# digipots.net
KiCad netlist of a schematic drawn in EAGLE
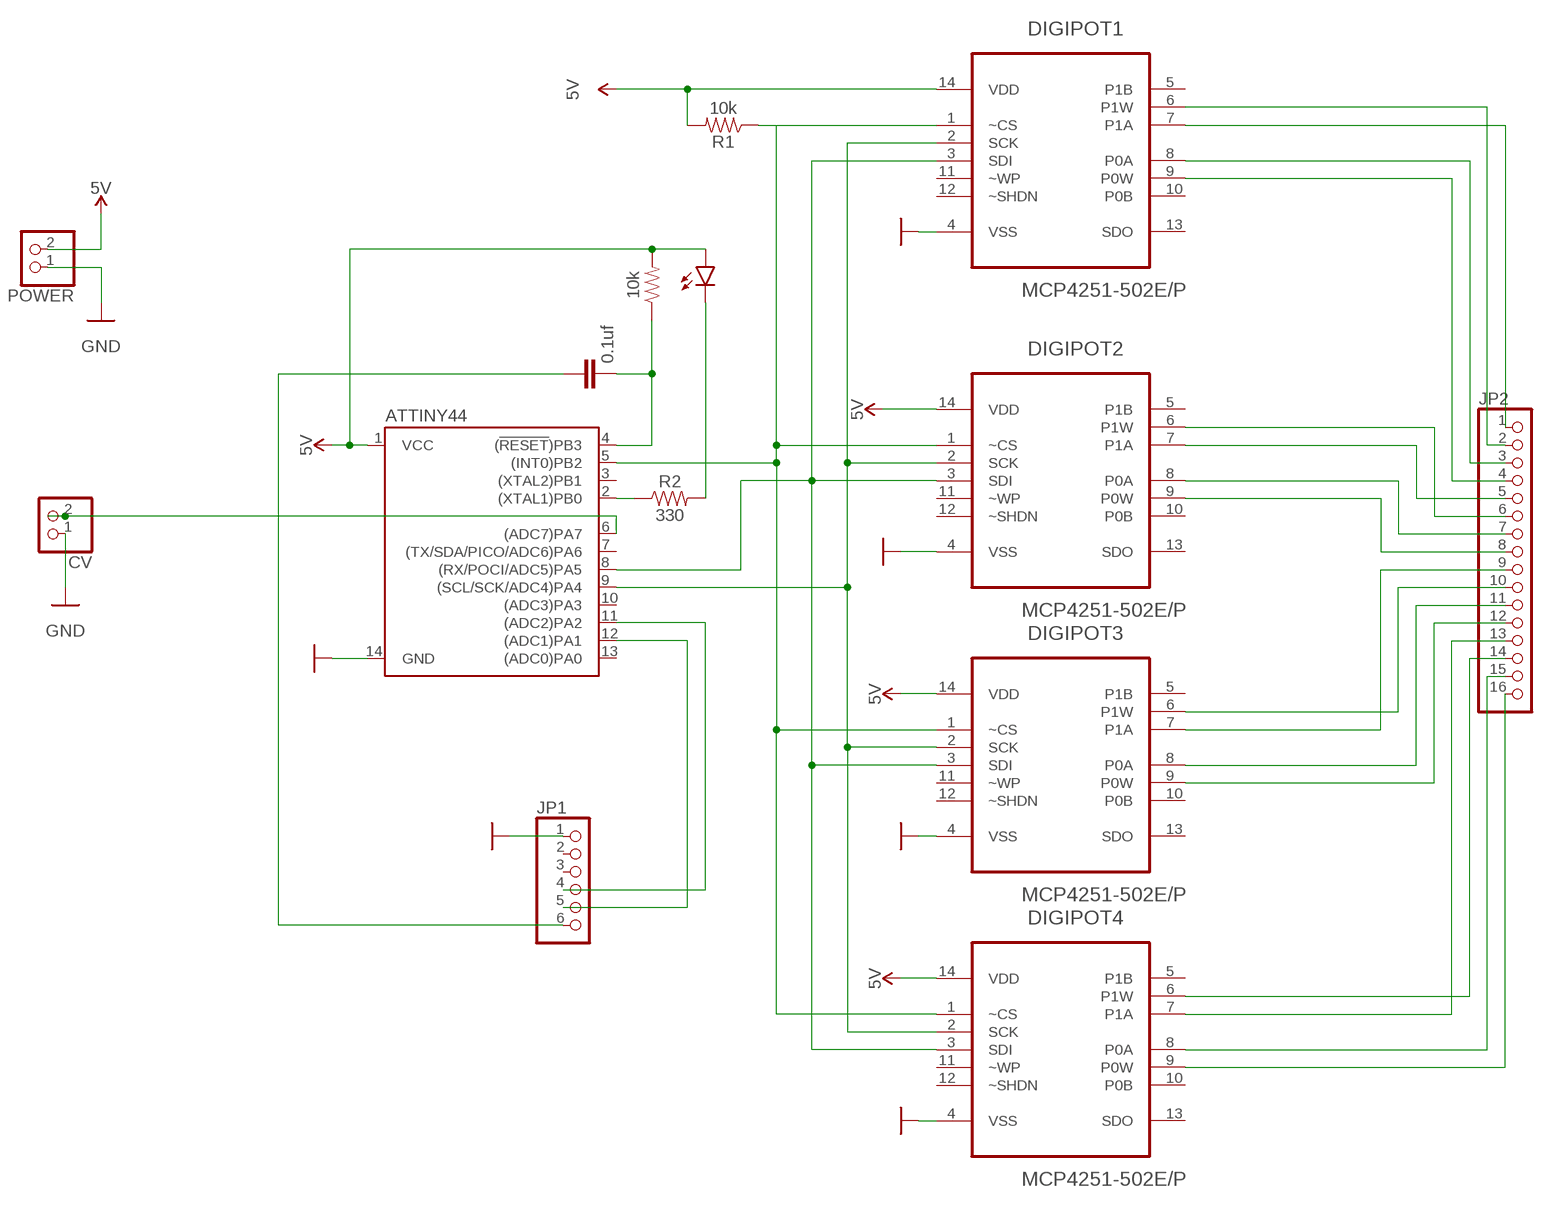
[diagram p0: schematic, sheet 1]

(export (version "E")
  (design (tool "Eeschema 10.0.6"))
  (components
    (comp (ref "ATTINY44")
      (value "ATTINY84ATTINY84-20PU")
      (footprint "eagle-import:DIP14")
      (libsource (lib "eagle-import") (part "ATTINY84ATTINY84-20PU"))
    )
    (comp (ref "C2")
      (value "0.1uf")
      (footprint "eagle-import:C025-024X044")
      (libsource (lib "eagle-import") (part "C-EU025-024X044"))
    )
    (comp (ref "CV")
      (value "PINHD-1X2")
      (footprint "eagle-import:1X02")
      (libsource (lib "eagle-import") (part "PINHD-1X2"))
    )
    (comp (ref "D1")
      (value "LED-5MM-KIT-NO-SILK")
      (footprint "eagle-import:LED_5MM-KIT-NO-SILK")
      (libsource (lib "eagle-import") (part "LED-5MM-KIT-NO-SILK"))
    )
    (comp (ref "DIGIPOT1")
      (value "MCP4251-502E/P")
      (footprint "eagle-import:DIP254P762X533-14")
      (fields (field (name "MF") "Microchip"))
      (libsource (lib "eagle-import") (part "MCP4251-502E/P"))
    )
    (comp (ref "DIGIPOT2")
      (value "MCP4251-502E/P")
      (footprint "eagle-import:DIP254P762X533-14")
      (fields (field (name "MF") "Microchip"))
      (libsource (lib "eagle-import") (part "MCP4251-502E/P"))
    )
    (comp (ref "DIGIPOT3")
      (value "MCP4251-502E/P")
      (footprint "eagle-import:DIP254P762X533-14")
      (fields (field (name "MF") "Microchip"))
      (libsource (lib "eagle-import") (part "MCP4251-502E/P"))
    )
    (comp (ref "DIGIPOT4")
      (value "MCP4251-502E/P")
      (footprint "eagle-import:DIP254P762X533-14")
      (fields (field (name "MF") "Microchip"))
      (libsource (lib "eagle-import") (part "MCP4251-502E/P"))
    )
    (comp (ref "JP1")
      (value "PINHD-1X6")
      (footprint "eagle-import:1X06")
      (libsource (lib "eagle-import") (part "PINHD-1X6"))
    )
    (comp (ref "JP2")
      (value "PINHD-1X16")
      (footprint "eagle-import:1X16")
      (libsource (lib "eagle-import") (part "PINHD-1X16"))
    )
    (comp (ref "POWER")
      (value "PINHD-1X2")
      (footprint "eagle-import:1X02")
      (libsource (lib "eagle-import") (part "PINHD-1X2"))
    )
    (comp (ref "R1")
      (value "10k")
      (footprint "eagle-import:AXIAL-0.3")
      (libsource (lib "eagle-import") (part "1KOHM-HORIZ-1/4W-5%"))
    )
    (comp (ref "R2")
      (value "330")
      (footprint "eagle-import:AXIAL-0.3")
      (libsource (lib "eagle-import") (part "1KOHM-HORIZ-1/4W-5%"))
    )
    (comp (ref "R3")
      (value "10k")
      (footprint "eagle-import:AXIAL-0.3")
      (libsource (lib "eagle-import") (part "1KOHM-HORIZ-1/4W-5%"))
    )
  )
  (nets
    (net (code "1") (name "5V") (class "Default")
      (node (ref "ATTINY44") (pin "1") (pinfunction "VCC_1") (pintype "bidirectional"))
      (node (ref "D1") (pin "A") (pinfunction "A_A") (pintype "passive"))
      (node (ref "DIGIPOT1") (pin "14") (pinfunction "VDD_14") (pintype "power_in"))
      (node (ref "DIGIPOT2") (pin "14") (pinfunction "VDD_14") (pintype "power_in"))
      (node (ref "DIGIPOT3") (pin "14") (pinfunction "VDD_14") (pintype "power_in"))
      (node (ref "DIGIPOT4") (pin "14") (pinfunction "VDD_14") (pintype "power_in"))
      (node (ref "POWER") (pin "2") (pinfunction "2_2") (pintype "passive"))
      (node (ref "R1") (pin "P$2") (pinfunction "2_P$2") (pintype "passive"))
      (node (ref "R3") (pin "P$2") (pinfunction "2_P$2") (pintype "passive"))
    )
    (net (code "2") (name "GND") (class "Default")
      (node (ref "ATTINY44") (pin "14") (pinfunction "GND_14") (pintype "bidirectional"))
      (node (ref "CV") (pin "1") (pinfunction "1_1") (pintype "passive"))
      (node (ref "DIGIPOT1") (pin "4") (pinfunction "VSS_4") (pintype "power_in"))
      (node (ref "DIGIPOT2") (pin "4") (pinfunction "VSS_4") (pintype "power_in"))
      (node (ref "DIGIPOT3") (pin "4") (pinfunction "VSS_4") (pintype "power_in"))
      (node (ref "DIGIPOT4") (pin "4") (pinfunction "VSS_4") (pintype "power_in"))
      (node (ref "JP1") (pin "1") (pinfunction "1_1") (pintype "passive"))
      (node (ref "POWER") (pin "1") (pinfunction "1_1") (pintype "passive"))
    )
    (net (code "3") (name "Net-(ATTINY44-(ADC1)PA1)") (class "Default")
      (node (ref "ATTINY44") (pin "12") (pinfunction "(ADC1)PA1_12") (pintype "bidirectional"))
      (node (ref "JP1") (pin "5") (pinfunction "5_5") (pintype "passive"))
    )
    (net (code "4") (name "Net-(ATTINY44-(ADC2)PA2)") (class "Default")
      (node (ref "ATTINY44") (pin "11") (pinfunction "(ADC2)PA2_11") (pintype "bidirectional"))
      (node (ref "JP1") (pin "4") (pinfunction "4_4") (pintype "passive"))
    )
    (net (code "5") (name "Net-(ATTINY44-(ADC7)PA7)") (class "Default")
      (node (ref "ATTINY44") (pin "6") (pinfunction "(ADC7)PA7_6") (pintype "bidirectional"))
      (node (ref "CV") (pin "2") (pinfunction "2_2") (pintype "passive"))
    )
    (net (code "6") (name "Net-(ATTINY44-(INT0)PB2)") (class "Default")
      (node (ref "ATTINY44") (pin "5") (pinfunction "(INT0)PB2_5") (pintype "bidirectional"))
      (node (ref "DIGIPOT1") (pin "1") (pinfunction "~{CS}_1") (pintype "input"))
      (node (ref "DIGIPOT2") (pin "1") (pinfunction "~{CS}_1") (pintype "input"))
      (node (ref "DIGIPOT3") (pin "1") (pinfunction "~{CS}_1") (pintype "input"))
      (node (ref "DIGIPOT4") (pin "1") (pinfunction "~{CS}_1") (pintype "input"))
      (node (ref "R1") (pin "P$1") (pinfunction "1_P$1") (pintype "passive"))
    )
    (net (code "7") (name "Net-(ATTINY44-(RX{slash}POCI{slash}ADC5)PA5)") (class "Default")
      (node (ref "ATTINY44") (pin "8") (pinfunction "(RX/POCI/ADC5)PA5_8") (pintype "bidirectional"))
      (node (ref "DIGIPOT1") (pin "3") (pinfunction "SDI_3") (pintype "input"))
      (node (ref "DIGIPOT2") (pin "3") (pinfunction "SDI_3") (pintype "input"))
      (node (ref "DIGIPOT3") (pin "3") (pinfunction "SDI_3") (pintype "input"))
      (node (ref "DIGIPOT4") (pin "3") (pinfunction "SDI_3") (pintype "input"))
    )
    (net (code "8") (name "Net-(ATTINY44-(SCL{slash}SCK{slash}ADC4)PA4)") (class "Default")
      (node (ref "ATTINY44") (pin "9") (pinfunction "(SCL/SCK/ADC4)PA4_9") (pintype "bidirectional"))
      (node (ref "DIGIPOT1") (pin "2") (pinfunction "SCK_2") (pintype "input"))
      (node (ref "DIGIPOT2") (pin "2") (pinfunction "SCK_2") (pintype "input"))
      (node (ref "DIGIPOT3") (pin "2") (pinfunction "SCK_2") (pintype "input"))
      (node (ref "DIGIPOT4") (pin "2") (pinfunction "SCK_2") (pintype "input"))
    )
    (net (code "9") (name "Net-(ATTINY44-(XTAL1)PB0)") (class "Default")
      (node (ref "ATTINY44") (pin "2") (pinfunction "(XTAL1)PB0_2") (pintype "bidirectional"))
      (node (ref "R2") (pin "P$1") (pinfunction "1_P$1") (pintype "passive"))
    )
    (net (code "10") (name "Net-(ATTINY44-(~{RESET})PB3)") (class "Default")
      (node (ref "ATTINY44") (pin "4") (pinfunction "(~{RESET})PB3_4") (pintype "bidirectional"))
      (node (ref "C2") (pin "2") (pinfunction "2_2") (pintype "passive"))
      (node (ref "R3") (pin "P$1") (pinfunction "1_P$1") (pintype "passive"))
    )
    (net (code "11") (name "Net-(C2-Pad1)") (class "Default")
      (node (ref "C2") (pin "1") (pinfunction "1_1") (pintype "passive"))
      (node (ref "JP1") (pin "6") (pinfunction "6_6") (pintype "passive"))
    )
    (net (code "12") (name "Net-(D1-C)") (class "Default")
      (node (ref "D1") (pin "K") (pinfunction "C_K") (pintype "passive"))
      (node (ref "R2") (pin "P$2") (pinfunction "2_P$2") (pintype "passive"))
    )
    (net (code "13") (name "Net-(DIGIPOT1-P0A)") (class "Default")
      (node (ref "DIGIPOT1") (pin "8") (pinfunction "P0A_8") (pintype "passive"))
      (node (ref "JP2") (pin "3") (pinfunction "3_3") (pintype "passive"))
    )
    (net (code "14") (name "Net-(DIGIPOT1-P0W)") (class "Default")
      (node (ref "DIGIPOT1") (pin "9") (pinfunction "P0W_9") (pintype "passive"))
      (node (ref "JP2") (pin "4") (pinfunction "4_4") (pintype "passive"))
    )
    (net (code "15") (name "Net-(DIGIPOT1-P1A)") (class "Default")
      (node (ref "DIGIPOT1") (pin "7") (pinfunction "P1A_7") (pintype "passive"))
      (node (ref "JP2") (pin "1") (pinfunction "1_1") (pintype "passive"))
    )
    (net (code "16") (name "Net-(DIGIPOT1-P1W)") (class "Default")
      (node (ref "DIGIPOT1") (pin "6") (pinfunction "P1W_6") (pintype "passive"))
      (node (ref "JP2") (pin "2") (pinfunction "2_2") (pintype "passive"))
    )
    (net (code "17") (name "Net-(DIGIPOT2-P0A)") (class "Default")
      (node (ref "DIGIPOT2") (pin "8") (pinfunction "P0A_8") (pintype "passive"))
      (node (ref "JP2") (pin "7") (pinfunction "7_7") (pintype "passive"))
    )
    (net (code "18") (name "Net-(DIGIPOT2-P0W)") (class "Default")
      (node (ref "DIGIPOT2") (pin "9") (pinfunction "P0W_9") (pintype "passive"))
      (node (ref "JP2") (pin "8") (pinfunction "8_8") (pintype "passive"))
    )
    (net (code "19") (name "Net-(DIGIPOT2-P1A)") (class "Default")
      (node (ref "DIGIPOT2") (pin "7") (pinfunction "P1A_7") (pintype "passive"))
      (node (ref "JP2") (pin "5") (pinfunction "5_5") (pintype "passive"))
    )
    (net (code "20") (name "Net-(DIGIPOT2-P1W)") (class "Default")
      (node (ref "DIGIPOT2") (pin "6") (pinfunction "P1W_6") (pintype "passive"))
      (node (ref "JP2") (pin "6") (pinfunction "6_6") (pintype "passive"))
    )
    (net (code "21") (name "Net-(DIGIPOT3-P0A)") (class "Default")
      (node (ref "DIGIPOT3") (pin "8") (pinfunction "P0A_8") (pintype "passive"))
      (node (ref "JP2") (pin "11") (pinfunction "11_11") (pintype "passive"))
    )
    (net (code "22") (name "Net-(DIGIPOT3-P0W)") (class "Default")
      (node (ref "DIGIPOT3") (pin "9") (pinfunction "P0W_9") (pintype "passive"))
      (node (ref "JP2") (pin "12") (pinfunction "12_12") (pintype "passive"))
    )
    (net (code "23") (name "Net-(DIGIPOT3-P1A)") (class "Default")
      (node (ref "DIGIPOT3") (pin "7") (pinfunction "P1A_7") (pintype "passive"))
      (node (ref "JP2") (pin "9") (pinfunction "9_9") (pintype "passive"))
    )
    (net (code "24") (name "Net-(DIGIPOT3-P1W)") (class "Default")
      (node (ref "DIGIPOT3") (pin "6") (pinfunction "P1W_6") (pintype "passive"))
      (node (ref "JP2") (pin "10") (pinfunction "10_10") (pintype "passive"))
    )
    (net (code "25") (name "Net-(DIGIPOT4-P0A)") (class "Default")
      (node (ref "DIGIPOT4") (pin "8") (pinfunction "P0A_8") (pintype "passive"))
      (node (ref "JP2") (pin "15") (pinfunction "15_15") (pintype "passive"))
    )
    (net (code "26") (name "Net-(DIGIPOT4-P0W)") (class "Default")
      (node (ref "DIGIPOT4") (pin "9") (pinfunction "P0W_9") (pintype "passive"))
      (node (ref "JP2") (pin "16") (pinfunction "16_16") (pintype "passive"))
    )
    (net (code "27") (name "Net-(DIGIPOT4-P1A)") (class "Default")
      (node (ref "DIGIPOT4") (pin "7") (pinfunction "P1A_7") (pintype "passive"))
      (node (ref "JP2") (pin "13") (pinfunction "13_13") (pintype "passive"))
    )
    (net (code "28") (name "Net-(DIGIPOT4-P1W)") (class "Default")
      (node (ref "DIGIPOT4") (pin "6") (pinfunction "P1W_6") (pintype "passive"))
      (node (ref "JP2") (pin "14") (pinfunction "14_14") (pintype "passive"))
    )
    (net (code "29") (name "unconnected-(ATTINY44-(ADC0)PA0-Pad13)") (class "Default")
      (node (ref "ATTINY44") (pin "13") (pinfunction "(ADC0)PA0_13") (pintype "bidirectional"))
    )
    (net (code "30") (name "unconnected-(ATTINY44-(ADC3)PA3-Pad10)") (class "Default")
      (node (ref "ATTINY44") (pin "10") (pinfunction "(ADC3)PA3_10") (pintype "bidirectional"))
    )
    (net (code "31") (name "unconnected-(ATTINY44-(TX{slash}SDA{slash}PICO{slash}ADC6)PA6-Pad7)") (class "Default")
      (node (ref "ATTINY44") (pin "7") (pinfunction "(TX/SDA/PICO/ADC6)PA6_7") (pintype "bidirectional"))
    )
    (net (code "32") (name "unconnected-(ATTINY44-(XTAL2)PB1-Pad3)") (class "Default")
      (node (ref "ATTINY44") (pin "3") (pinfunction "(XTAL2)PB1_3") (pintype "bidirectional"))
    )
    (net (code "33") (name "unconnected-(DIGIPOT1-P0B-Pad10)") (class "Default")
      (node (ref "DIGIPOT1") (pin "10") (pinfunction "P0B_10") (pintype "passive"))
    )
    (net (code "34") (name "unconnected-(DIGIPOT1-P1B-Pad5)") (class "Default")
      (node (ref "DIGIPOT1") (pin "5") (pinfunction "P1B_5") (pintype "passive"))
    )
    (net (code "35") (name "unconnected-(DIGIPOT1-SDO-Pad13)") (class "Default")
      (node (ref "DIGIPOT1") (pin "13") (pinfunction "SDO_13") (pintype "output"))
    )
    (net (code "36") (name "unconnected-(DIGIPOT1-~{SHDN}-Pad12)") (class "Default")
      (node (ref "DIGIPOT1") (pin "12") (pinfunction "~{SHDN}_12") (pintype "input"))
    )
    (net (code "37") (name "unconnected-(DIGIPOT1-~{WP}-Pad11)") (class "Default")
      (node (ref "DIGIPOT1") (pin "11") (pinfunction "~{WP}_11") (pintype "input"))
    )
    (net (code "38") (name "unconnected-(DIGIPOT2-P0B-Pad10)") (class "Default")
      (node (ref "DIGIPOT2") (pin "10") (pinfunction "P0B_10") (pintype "passive"))
    )
    (net (code "39") (name "unconnected-(DIGIPOT2-P1B-Pad5)") (class "Default")
      (node (ref "DIGIPOT2") (pin "5") (pinfunction "P1B_5") (pintype "passive"))
    )
    (net (code "40") (name "unconnected-(DIGIPOT2-SDO-Pad13)") (class "Default")
      (node (ref "DIGIPOT2") (pin "13") (pinfunction "SDO_13") (pintype "output"))
    )
    (net (code "41") (name "unconnected-(DIGIPOT2-~{SHDN}-Pad12)") (class "Default")
      (node (ref "DIGIPOT2") (pin "12") (pinfunction "~{SHDN}_12") (pintype "input"))
    )
    (net (code "42") (name "unconnected-(DIGIPOT2-~{WP}-Pad11)") (class "Default")
      (node (ref "DIGIPOT2") (pin "11") (pinfunction "~{WP}_11") (pintype "input"))
    )
    (net (code "43") (name "unconnected-(DIGIPOT3-P0B-Pad10)") (class "Default")
      (node (ref "DIGIPOT3") (pin "10") (pinfunction "P0B_10") (pintype "passive"))
    )
    (net (code "44") (name "unconnected-(DIGIPOT3-P1B-Pad5)") (class "Default")
      (node (ref "DIGIPOT3") (pin "5") (pinfunction "P1B_5") (pintype "passive"))
    )
    (net (code "45") (name "unconnected-(DIGIPOT3-SDO-Pad13)") (class "Default")
      (node (ref "DIGIPOT3") (pin "13") (pinfunction "SDO_13") (pintype "output"))
    )
    (net (code "46") (name "unconnected-(DIGIPOT3-~{SHDN}-Pad12)") (class "Default")
      (node (ref "DIGIPOT3") (pin "12") (pinfunction "~{SHDN}_12") (pintype "input"))
    )
    (net (code "47") (name "unconnected-(DIGIPOT3-~{WP}-Pad11)") (class "Default")
      (node (ref "DIGIPOT3") (pin "11") (pinfunction "~{WP}_11") (pintype "input"))
    )
    (net (code "48") (name "unconnected-(DIGIPOT4-P0B-Pad10)") (class "Default")
      (node (ref "DIGIPOT4") (pin "10") (pinfunction "P0B_10") (pintype "passive"))
    )
    (net (code "49") (name "unconnected-(DIGIPOT4-P1B-Pad5)") (class "Default")
      (node (ref "DIGIPOT4") (pin "5") (pinfunction "P1B_5") (pintype "passive"))
    )
    (net (code "50") (name "unconnected-(DIGIPOT4-SDO-Pad13)") (class "Default")
      (node (ref "DIGIPOT4") (pin "13") (pinfunction "SDO_13") (pintype "output"))
    )
    (net (code "51") (name "unconnected-(DIGIPOT4-~{SHDN}-Pad12)") (class "Default")
      (node (ref "DIGIPOT4") (pin "12") (pinfunction "~{SHDN}_12") (pintype "input"))
    )
    (net (code "52") (name "unconnected-(DIGIPOT4-~{WP}-Pad11)") (class "Default")
      (node (ref "DIGIPOT4") (pin "11") (pinfunction "~{WP}_11") (pintype "input"))
    )
    (net (code "53") (name "unconnected-(JP1-Pad2)") (class "Default")
      (node (ref "JP1") (pin "2") (pinfunction "2_2") (pintype "passive"))
    )
    (net (code "54") (name "unconnected-(JP1-Pad3)") (class "Default")
      (node (ref "JP1") (pin "3") (pinfunction "3_3") (pintype "passive"))
    )
  )
)
